# Elekid_MCU.net
KiCad netlist of a schematic drawn in Altium Designer
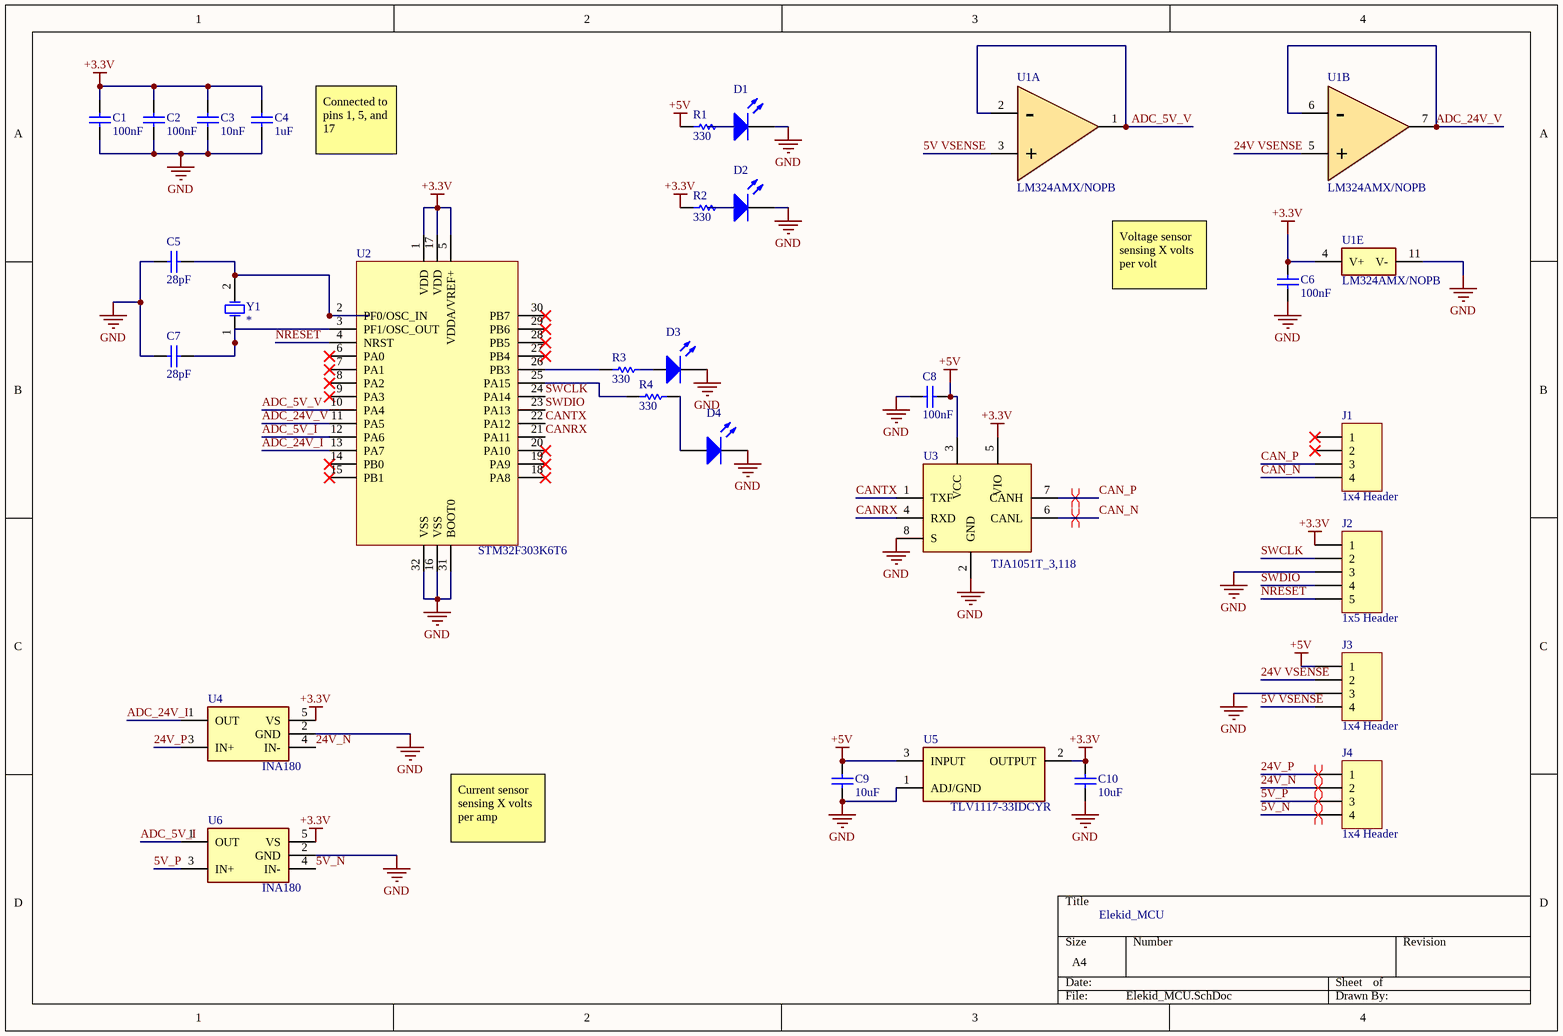
[diagram p0: Elekid_MCU.SchDoc]

(export (version "E")
  (design (tool "Eeschema 10.0.6"))
  (components
    (comp (ref "C1")
      (value "100nF")
      (footprint "0805 - Capacitor")
      (description "Nonpolarized Capacitor")
      (fields (field (name "Comment") "Capacitor - Nonpolarized"))
      (libsource (lib "General") (part "Capacitor - Nonpolarized"))
    )
    (comp (ref "C2")
      (value "100nF")
      (footprint "0805 - Capacitor")
      (description "Nonpolarized Capacitor")
      (fields (field (name "Comment") "Capacitor - Nonpolarized"))
      (libsource (lib "General") (part "Capacitor - Nonpolarized"))
    )
    (comp (ref "C3")
      (value "10nF")
      (footprint "0805 - Capacitor")
      (description "Nonpolarized Capacitor")
      (fields (field (name "Comment") "Capacitor - Nonpolarized"))
      (libsource (lib "General") (part "Capacitor - Nonpolarized"))
    )
    (comp (ref "C4")
      (value "1uF")
      (footprint "0805 - Capacitor")
      (description "Nonpolarized Capacitor")
      (fields (field (name "Comment") "Capacitor - Nonpolarized"))
      (libsource (lib "General") (part "Capacitor - Nonpolarized"))
    )
    (comp (ref "C5")
      (value "28pF")
      (footprint "0805 - Capacitor")
      (description "Nonpolarized Capacitor")
      (fields (field (name "Comment") "Capacitor - Nonpolarized"))
      (libsource (lib "General") (part "Capacitor - Nonpolarized"))
    )
    (comp (ref "C6")
      (value "100nF")
      (footprint "0805 - Capacitor")
      (description "Nonpolarized Capacitor")
      (fields (field (name "Comment") "Capacitor - Nonpolarized"))
      (libsource (lib "General") (part "Capacitor - Nonpolarized"))
    )
    (comp (ref "C7")
      (value "28pF")
      (footprint "0805 - Capacitor")
      (description "Nonpolarized Capacitor")
      (fields (field (name "Comment") "Capacitor - Nonpolarized"))
      (libsource (lib "General") (part "Capacitor - Nonpolarized"))
    )
    (comp (ref "C8")
      (value "100nF")
      (footprint "0805 - Capacitor")
      (description "Nonpolarized Capacitor")
      (fields (field (name "Comment") "Capacitor - Nonpolarized"))
      (libsource (lib "General") (part "Capacitor - Nonpolarized"))
    )
    (comp (ref "C9")
      (value "10uF")
      (footprint "0805 - Capacitor")
      (description "Nonpolarized Capacitor")
      (fields (field (name "Comment") "Capacitor - Nonpolarized"))
      (libsource (lib "General") (part "Capacitor - Nonpolarized"))
    )
    (comp (ref "C10")
      (value "10uF")
      (footprint "0805 - Capacitor")
      (description "Nonpolarized Capacitor")
      (fields (field (name "Comment") "Capacitor - Nonpolarized"))
      (libsource (lib "General") (part "Capacitor - Nonpolarized"))
    )
    (comp (ref "D1")
      (value "LED")
      (footprint "0805 - Resistor")
      (description "Light Emitting Diode")
      (libsource (lib "General") (part "LED"))
    )
    (comp (ref "D2")
      (value "LED")
      (footprint "0805 - Resistor")
      (description "Light Emitting Diode")
      (libsource (lib "General") (part "LED"))
    )
    (comp (ref "D3")
      (value "LED")
      (footprint "0805 - Resistor")
      (description "Light Emitting Diode")
      (libsource (lib "General") (part "LED"))
    )
    (comp (ref "D4")
      (value "LED")
      (footprint "0805 - Resistor")
      (description "Light Emitting Diode")
      (libsource (lib "General") (part "LED"))
    )
    (comp (ref "J1")
      (value "1x4 Header")
      (footprint "B4B-XH")
      (description "1x4 Pin Header")
      (libsource (lib "GeneralConnectors") (part "1x4 Header"))
    )
    (comp (ref "J2")
      (value "1x5 Header")
      (footprint "HDR1X5")
      (description "1x5 Pin Header")
      (libsource (lib "GeneralConnectors") (part "1x5 Header"))
    )
    (comp (ref "J3")
      (value "1x4 Header")
      (footprint "B4B-XH")
      (description "1x4 Pin Header")
      (libsource (lib "GeneralConnectors") (part "1x4 Header"))
    )
    (comp (ref "J4")
      (value "1x4 Header")
      (footprint "B4B-XH")
      (description "1x4 Pin Header")
      (libsource (lib "GeneralConnectors") (part "1x4 Header"))
    )
    (comp (ref "R1")
      (value "330")
      (footprint "0603 - Resistor")
      (description "Resistor")
      (libsource (lib "General") (part "Resistor"))
    )
    (comp (ref "R2")
      (value "330")
      (footprint "0603 - Resistor")
      (description "Resistor")
      (libsource (lib "General") (part "Resistor"))
    )
    (comp (ref "R3")
      (value "330")
      (footprint "0603 - Resistor")
      (description "Resistor")
      (libsource (lib "General") (part "Resistor"))
    )
    (comp (ref "R4")
      (value "330")
      (footprint "0603 - Resistor")
      (description "Resistor")
      (libsource (lib "General") (part "Resistor"))
    )
    (comp (ref "U1")
      (value "LM324AMX/NOPB")
      (footprint "LM324AMX/NOPB")
      (description "Gen Purp 4Ch Opamp")
      (libsource (lib "GeneralComponents") (part "LM324AMX/NOPB"))
    )
    (comp (ref "U2")
      (value "STM32F303K6T6")
      (footprint "QFP80P900X900X160-32N")
      (description "Integrated Circuit")
      (libsource (lib "Embedded") (part "STM32F303K6T6"))
    )
    (comp (ref "U3")
      (value "TJA1051T_3,118")
      (footprint "TJA1051T/3,118")
      (description "CAN Transceiver IC 4.5V-5.5V 250ns")
      (fields (field (name "MANUFACTURER") "NXP") (field (name "MANUFACTURER PART NUMBER") "TJA1051T/3,118"))
      (libsource (lib "GeneralComponents") (part "TJA1051T_3,118"))
    )
    (comp (ref "U4")
      (value "INA180")
      (footprint "INA180")
      (description "0V to 26V Current Sense Amplifier")
      (fields
        (field (name "MANUFACTURER") "Texas Instruments")
        (field (name "MANUFACTURER PART NUMBER") "INA180A2IDBVR")
      )
      (libsource (lib "GeneralComponents") (part "INA180"))
    )
    (comp (ref "U5")
      (value "TLV1117-33IDCYR")
      (footprint "TLV1117")
      (description "Linear Voltage Regulator IC 3.3V 800MA SOT223-4")
      (fields (field (name "MANUFACTURER") "Texas Instruments"))
      (libsource (lib "GeneralComponents") (part "TLV1117-33IDCYR"))
    )
    (comp (ref "U6")
      (value "INA180")
      (footprint "INA180")
      (description "0V to 26V Current Sense Amplifier")
      (fields
        (field (name "MANUFACTURER") "Texas Instruments")
        (field (name "MANUFACTURER PART NUMBER") "INA180A2IDBVR")
      )
      (libsource (lib "GeneralComponents") (part "INA180"))
    )
    (comp (ref "Y1")
      (value "Oscillator")
      (footprint "2-SMD NO LEAD CRSYSTAL")
      (description "Crystal Oscillator")
      (fields (field (name "ALTIUM_VALUE") "*"))
      (libsource (lib "General") (part "Oscillator"))
    )
  )
  (nets
    (net (code "1") (name "+3.3V") (class "Default")
      (node (ref "C1") (pin "2") (pinfunction "2_2") (pintype "passive"))
      (node (ref "C10") (pin "2") (pinfunction "2_2") (pintype "passive"))
      (node (ref "C2") (pin "2") (pinfunction "2_2") (pintype "passive"))
      (node (ref "C3") (pin "2") (pinfunction "2_2") (pintype "passive"))
      (node (ref "C4") (pin "2") (pinfunction "2_2") (pintype "passive"))
      (node (ref "C6") (pin "2") (pinfunction "2_2") (pintype "passive"))
      (node (ref "J2") (pin "1") (pinfunction "1_1") (pintype "passive"))
      (node (ref "R2") (pin "1") (pinfunction "1_1") (pintype "passive"))
      (node (ref "U1") (pin "4") (pinfunction "V+_4") (pintype "passive"))
      (node (ref "U2") (pin "1") (pinfunction "VDD_1") (pintype "passive"))
      (node (ref "U2") (pin "17") (pinfunction "VDD_17") (pintype "passive"))
      (node (ref "U2") (pin "5") (pinfunction "VDDA/VREF+_5") (pintype "passive"))
      (node (ref "U3") (pin "5") (pinfunction "VIO_5") (pintype "passive"))
      (node (ref "U4") (pin "5") (pinfunction "VS_5") (pintype "passive"))
      (node (ref "U5") (pin "2") (pinfunction "OUTPUT_2") (pintype "passive"))
      (node (ref "U6") (pin "5") (pinfunction "VS_5") (pintype "passive"))
    )
    (net (code "2") (name "+5V") (class "Default")
      (node (ref "C8") (pin "2") (pinfunction "2_2") (pintype "passive"))
      (node (ref "C9") (pin "2") (pinfunction "2_2") (pintype "passive"))
      (node (ref "J3") (pin "1") (pinfunction "1_1") (pintype "passive"))
      (node (ref "R1") (pin "1") (pinfunction "1_1") (pintype "passive"))
      (node (ref "U3") (pin "3") (pinfunction "VCC_3") (pintype "passive"))
      (node (ref "U5") (pin "3") (pinfunction "INPUT_3") (pintype "passive"))
    )
    (net (code "3") (name "/5V VSENSE") (class "Default")
      (node (ref "J3") (pin "4") (pinfunction "4_4") (pintype "passive"))
      (node (ref "U1") (pin "3") (pinfunction "+_3") (pintype "passive"))
    )
    (net (code "4") (name "/5V_N") (class "Default")
      (node (ref "J4") (pin "4") (pinfunction "4_4") (pintype "passive"))
      (node (ref "U6") (pin "4") (pinfunction "IN-_4") (pintype "passive"))
    )
    (net (code "5") (name "/5V_P") (class "Default")
      (node (ref "J4") (pin "3") (pinfunction "3_3") (pintype "passive"))
      (node (ref "U6") (pin "3") (pinfunction "IN+_3") (pintype "passive"))
    )
    (net (code "6") (name "/24V VSENSE") (class "Default")
      (node (ref "J3") (pin "2") (pinfunction "2_2") (pintype "passive"))
      (node (ref "U1") (pin "5") (pinfunction "+_5") (pintype "passive"))
    )
    (net (code "7") (name "/24V_N") (class "Default")
      (node (ref "J4") (pin "2") (pinfunction "2_2") (pintype "passive"))
      (node (ref "U4") (pin "4") (pinfunction "IN-_4") (pintype "passive"))
    )
    (net (code "8") (name "/24V_P") (class "Default")
      (node (ref "J4") (pin "1") (pinfunction "1_1") (pintype "passive"))
      (node (ref "U4") (pin "3") (pinfunction "IN+_3") (pintype "passive"))
    )
    (net (code "9") (name "/ADC_5V_I") (class "Default")
      (node (ref "U2") (pin "12") (pinfunction "PA6_12") (pintype "passive"))
      (node (ref "U6") (pin "1") (pinfunction "OUT_1") (pintype "passive"))
    )
    (net (code "10") (name "/ADC_5V_V") (class "Default")
      (node (ref "U1") (pin "1") (pinfunction "14_1") (pintype "passive"))
      (node (ref "U1") (pin "2") (pinfunction "-_2") (pintype "passive"))
      (node (ref "U2") (pin "10") (pinfunction "PA4_10") (pintype "passive"))
    )
    (net (code "11") (name "/ADC_24V_I") (class "Default")
      (node (ref "U2") (pin "13") (pinfunction "PA7_13") (pintype "passive"))
      (node (ref "U4") (pin "1") (pinfunction "OUT_1") (pintype "passive"))
    )
    (net (code "12") (name "/ADC_24V_V") (class "Default")
      (node (ref "U1") (pin "6") (pinfunction "-_6") (pintype "passive"))
      (node (ref "U1") (pin "7") (pinfunction "14_7") (pintype "passive"))
      (node (ref "U2") (pin "11") (pinfunction "PA5_11") (pintype "passive"))
    )
    (net (code "13") (name "/CANRX") (class "Default")
      (node (ref "U2") (pin "21") (pinfunction "PA11_21") (pintype "passive"))
      (node (ref "U3") (pin "4") (pinfunction "RXD_4") (pintype "passive"))
    )
    (net (code "14") (name "/CANTX") (class "Default")
      (node (ref "U2") (pin "22") (pinfunction "PA12_22") (pintype "passive"))
      (node (ref "U3") (pin "1") (pinfunction "TXF_1") (pintype "passive"))
    )
    (net (code "15") (name "/CAN_N") (class "Default")
      (node (ref "J1") (pin "4") (pinfunction "4_4") (pintype "passive"))
      (node (ref "U3") (pin "6") (pinfunction "CANL_6") (pintype "passive"))
    )
    (net (code "16") (name "/CAN_P") (class "Default")
      (node (ref "J1") (pin "3") (pinfunction "3_3") (pintype "passive"))
      (node (ref "U3") (pin "7") (pinfunction "CANH_7") (pintype "passive"))
    )
    (net (code "17") (name "/NRESET") (class "Default")
      (node (ref "J2") (pin "5") (pinfunction "5_5") (pintype "passive"))
      (node (ref "U2") (pin "4") (pinfunction "NRST_4") (pintype "passive"))
    )
    (net (code "18") (name "/SWCLK") (class "Default")
      (node (ref "J2") (pin "2") (pinfunction "2_2") (pintype "passive"))
      (node (ref "U2") (pin "24") (pinfunction "PA14_24") (pintype "passive"))
    )
    (net (code "19") (name "/SWDIO") (class "Default")
      (node (ref "J2") (pin "4") (pinfunction "4_4") (pintype "passive"))
      (node (ref "U2") (pin "23") (pinfunction "PA13_23") (pintype "passive"))
    )
    (net (code "20") (name "GND") (class "Default")
      (node (ref "C1") (pin "1") (pinfunction "1_1") (pintype "passive"))
      (node (ref "C10") (pin "1") (pinfunction "1_1") (pintype "passive"))
      (node (ref "C2") (pin "1") (pinfunction "1_1") (pintype "passive"))
      (node (ref "C3") (pin "1") (pinfunction "1_1") (pintype "passive"))
      (node (ref "C4") (pin "1") (pinfunction "1_1") (pintype "passive"))
      (node (ref "C5") (pin "1") (pinfunction "1_1") (pintype "passive"))
      (node (ref "C6") (pin "1") (pinfunction "1_1") (pintype "passive"))
      (node (ref "C7") (pin "1") (pinfunction "1_1") (pintype "passive"))
      (node (ref "C8") (pin "1") (pinfunction "1_1") (pintype "passive"))
      (node (ref "C9") (pin "1") (pinfunction "1_1") (pintype "passive"))
      (node (ref "D1") (pin "2") (pinfunction "K_2") (pintype "passive"))
      (node (ref "D2") (pin "2") (pinfunction "K_2") (pintype "passive"))
      (node (ref "D3") (pin "2") (pinfunction "K_2") (pintype "passive"))
      (node (ref "D4") (pin "2") (pinfunction "K_2") (pintype "passive"))
      (node (ref "J2") (pin "3") (pinfunction "3_3") (pintype "passive"))
      (node (ref "J3") (pin "3") (pinfunction "3_3") (pintype "passive"))
      (node (ref "U1") (pin "11") (pinfunction "V-_11") (pintype "passive"))
      (node (ref "U2") (pin "16") (pinfunction "VSS_16") (pintype "passive"))
      (node (ref "U2") (pin "31") (pinfunction "BOOT0_31") (pintype "passive"))
      (node (ref "U2") (pin "32") (pinfunction "VSS_32") (pintype "passive"))
      (node (ref "U3") (pin "2") (pinfunction "GND_2") (pintype "passive"))
      (node (ref "U3") (pin "8") (pinfunction "S_8") (pintype "passive"))
      (node (ref "U4") (pin "2") (pinfunction "GND_2") (pintype "passive"))
      (node (ref "U5") (pin "1") (pinfunction "ADJ/GND_1") (pintype "passive"))
      (node (ref "U6") (pin "2") (pinfunction "GND_2") (pintype "passive"))
    )
    (net (code "21") (name "Net-(D1-A)") (class "Default")
      (node (ref "D1") (pin "1") (pinfunction "A_1") (pintype "passive"))
      (node (ref "R1") (pin "2") (pinfunction "2_2") (pintype "passive"))
    )
    (net (code "22") (name "Net-(D2-A)") (class "Default")
      (node (ref "D2") (pin "1") (pinfunction "A_1") (pintype "passive"))
      (node (ref "R2") (pin "2") (pinfunction "2_2") (pintype "passive"))
    )
    (net (code "23") (name "Net-(D3-A)") (class "Default")
      (node (ref "D3") (pin "1") (pinfunction "A_1") (pintype "passive"))
      (node (ref "R3") (pin "2") (pinfunction "2_2") (pintype "passive"))
    )
    (net (code "24") (name "Net-(D4-A)") (class "Default")
      (node (ref "D4") (pin "1") (pinfunction "A_1") (pintype "passive"))
      (node (ref "R4") (pin "2") (pinfunction "2_2") (pintype "passive"))
    )
    (net (code "25") (name "Net-(U2-PA15)") (class "Default")
      (node (ref "R4") (pin "1") (pinfunction "1_1") (pintype "passive"))
      (node (ref "U2") (pin "25") (pinfunction "PA15_25") (pintype "passive"))
    )
    (net (code "26") (name "Net-(U2-PB3)") (class "Default")
      (node (ref "R3") (pin "1") (pinfunction "1_1") (pintype "passive"))
      (node (ref "U2") (pin "26") (pinfunction "PB3_26") (pintype "passive"))
    )
    (net (code "27") (name "Net-(U2-PF0{slash}OSC_IN)") (class "Default")
      (node (ref "C5") (pin "2") (pinfunction "2_2") (pintype "passive"))
      (node (ref "U2") (pin "2") (pinfunction "PF0/OSC_IN_2") (pintype "passive"))
      (node (ref "Y1") (pin "2") (pinfunction "OSC2_2") (pintype "passive"))
    )
    (net (code "28") (name "Net-(U2-PF1{slash}OSC_OUT)") (class "Default")
      (node (ref "C7") (pin "2") (pinfunction "2_2") (pintype "passive"))
      (node (ref "U2") (pin "3") (pinfunction "PF1/OSC_OUT_3") (pintype "passive"))
      (node (ref "Y1") (pin "1") (pinfunction "OSC1_1") (pintype "passive"))
    )
    (net (code "29") (name "unconnected-(J1-Pad1)") (class "Default")
      (node (ref "J1") (pin "1") (pinfunction "1_1") (pintype "passive+no_connect"))
    )
    (net (code "30") (name "unconnected-(J1-Pad2)") (class "Default")
      (node (ref "J1") (pin "2") (pinfunction "2_2") (pintype "passive+no_connect"))
    )
    (net (code "31") (name "unconnected-(U2-PA0-Pad6)") (class "Default")
      (node (ref "U2") (pin "6") (pinfunction "PA0_6") (pintype "passive+no_connect"))
    )
    (net (code "32") (name "unconnected-(U2-PA1-Pad7)") (class "Default")
      (node (ref "U2") (pin "7") (pinfunction "PA1_7") (pintype "passive+no_connect"))
    )
    (net (code "33") (name "unconnected-(U2-PA2-Pad8)") (class "Default")
      (node (ref "U2") (pin "8") (pinfunction "PA2_8") (pintype "passive+no_connect"))
    )
    (net (code "34") (name "unconnected-(U2-PA3-Pad9)") (class "Default")
      (node (ref "U2") (pin "9") (pinfunction "PA3_9") (pintype "passive+no_connect"))
    )
    (net (code "35") (name "unconnected-(U2-PA8-Pad18)") (class "Default")
      (node (ref "U2") (pin "18") (pinfunction "PA8_18") (pintype "passive+no_connect"))
    )
    (net (code "36") (name "unconnected-(U2-PA9-Pad19)") (class "Default")
      (node (ref "U2") (pin "19") (pinfunction "PA9_19") (pintype "passive+no_connect"))
    )
    (net (code "37") (name "unconnected-(U2-PA10-Pad20)") (class "Default")
      (node (ref "U2") (pin "20") (pinfunction "PA10_20") (pintype "passive+no_connect"))
    )
    (net (code "38") (name "unconnected-(U2-PB0-Pad14)") (class "Default")
      (node (ref "U2") (pin "14") (pinfunction "PB0_14") (pintype "passive+no_connect"))
    )
    (net (code "39") (name "unconnected-(U2-PB1-Pad15)") (class "Default")
      (node (ref "U2") (pin "15") (pinfunction "PB1_15") (pintype "passive+no_connect"))
    )
    (net (code "40") (name "unconnected-(U2-PB4-Pad27)") (class "Default")
      (node (ref "U2") (pin "27") (pinfunction "PB4_27") (pintype "passive+no_connect"))
    )
    (net (code "41") (name "unconnected-(U2-PB5-Pad28)") (class "Default")
      (node (ref "U2") (pin "28") (pinfunction "PB5_28") (pintype "passive+no_connect"))
    )
    (net (code "42") (name "unconnected-(U2-PB6-Pad29)") (class "Default")
      (node (ref "U2") (pin "29") (pinfunction "PB6_29") (pintype "passive+no_connect"))
    )
    (net (code "43") (name "unconnected-(U2-PB7-Pad30)") (class "Default")
      (node (ref "U2") (pin "30") (pinfunction "PB7_30") (pintype "passive+no_connect"))
    )
  )
)
